# SCH_Driver_RL.net
KiCad netlist of a schematic drawn in Altium Designer
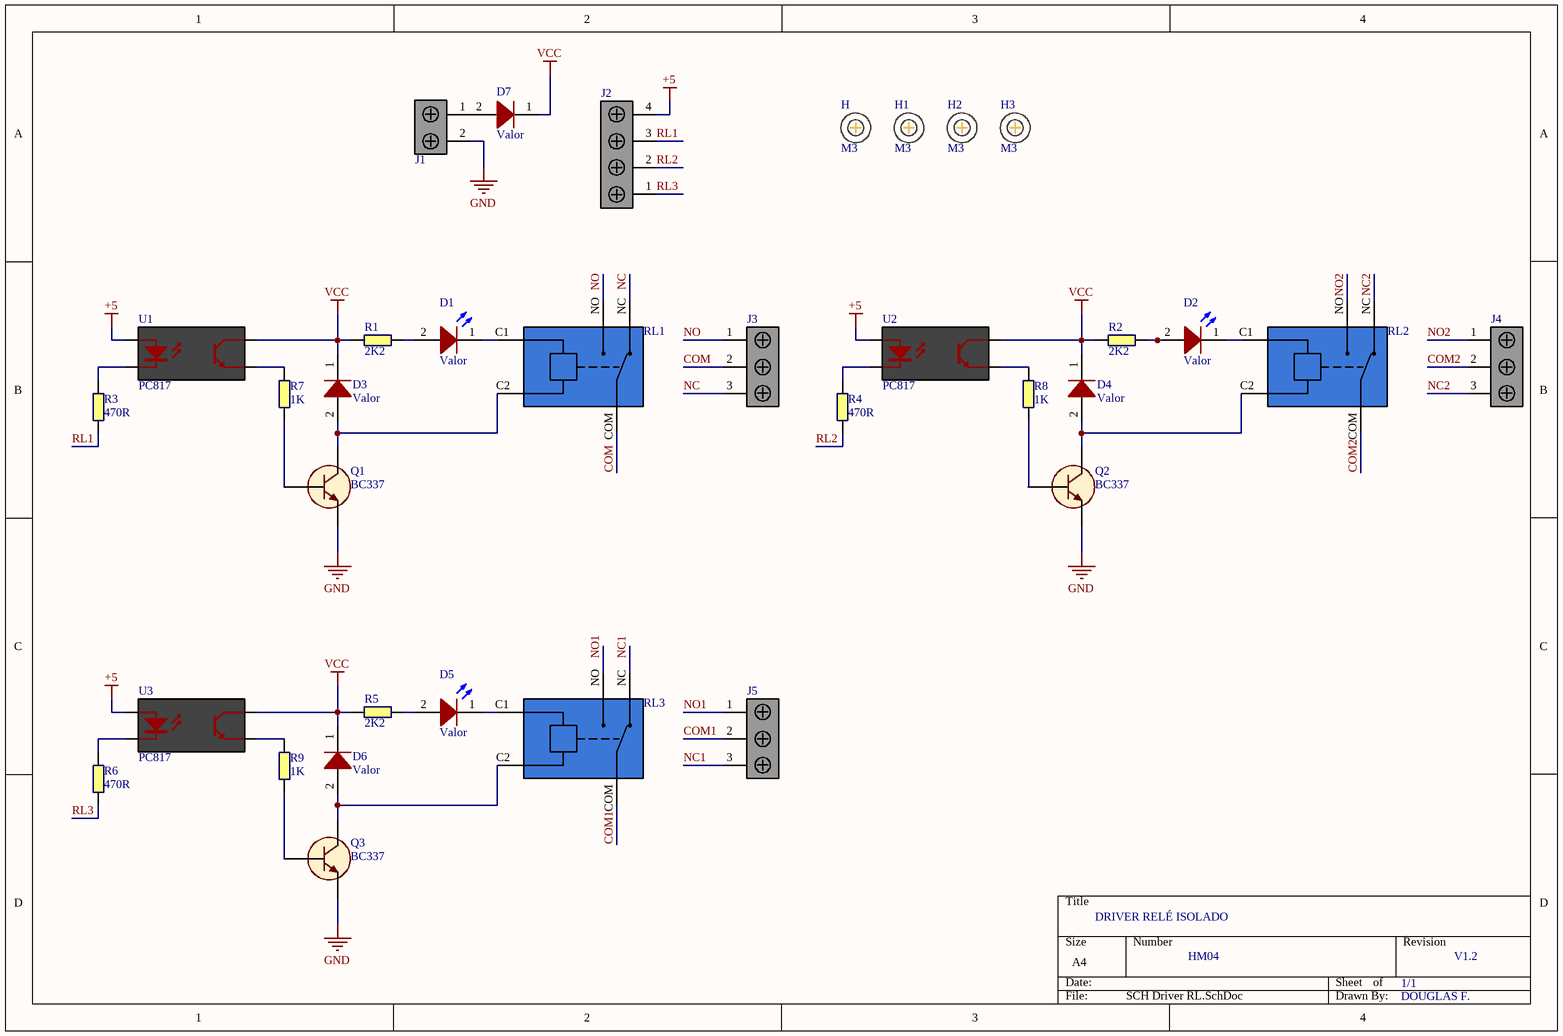
[diagram p0: SCH Driver RL.SchDoc]

(export (version "E")
  (design (tool "Eeschema 10.0.6"))
  (components
    (comp (ref "D1")
      (value "Valor")
      (footprint "LED 3MM")
      (description "Typical RED, GREEN, YELLOW, AMBER GaAs LED")
      (fields (field (name "PUBLISHER") "Altium Limited"))
      (libsource (lib "Driver relé") (part "LED"))
    )
    (comp (ref "D2")
      (value "Valor")
      (footprint "LED 3MM")
      (description "Typical RED, GREEN, YELLOW, AMBER GaAs LED")
      (fields (field (name "PUBLISHER") "Altium Limited"))
      (libsource (lib "Driver relé") (part "LED"))
    )
    (comp (ref "D3")
      (value "Valor")
      (footprint "1N4148 DO-35")
      (description "Diodo rapido")
      (fields (field (name "PUBLISHER") "Altium Limited"))
      (libsource (lib "Driver relé") (part "DIODO 1N4148"))
    )
    (comp (ref "D4")
      (value "Valor")
      (footprint "1N4148 DO-35")
      (description "Diodo rapido")
      (fields (field (name "PUBLISHER") "Altium Limited"))
      (libsource (lib "Driver relé") (part "DIODO 1N4148"))
    )
    (comp (ref "D5")
      (value "Valor")
      (footprint "LED 3MM")
      (description "Typical RED, GREEN, YELLOW, AMBER GaAs LED")
      (fields (field (name "PUBLISHER") "Altium Limited"))
      (libsource (lib "Driver relé") (part "LED"))
    )
    (comp (ref "D6")
      (value "Valor")
      (footprint "1N4148 DO-35")
      (description "Diodo rapido")
      (fields (field (name "PUBLISHER") "Altium Limited"))
      (libsource (lib "Driver relé") (part "DIODO 1N4148"))
    )
    (comp (ref "D7")
      (value "Valor")
      (footprint "1N4007 DO-41")
      (description "Diodo rapido")
      (fields (field (name "PUBLISHER") "Altium Limited"))
      (libsource (lib "Driver relé") (part "DIODO 1N4007"))
    )
    (comp (ref "H") (value "M3") (footprint "Parafuso M3") (libsource (lib "Driver relé") (part "Furo M3")))
    (comp (ref "H1") (value "M3") (footprint "Parafuso M3") (libsource (lib "Driver relé") (part "Furo M3")))
    (comp (ref "H2") (value "M3") (footprint "Parafuso M3") (libsource (lib "Driver relé") (part "Furo M3")))
    (comp (ref "H3") (value "M3") (footprint "Parafuso M3") (libsource (lib "Driver relé") (part "Furo M3")))
    (comp (ref "J1")
      (value "Conector 2v Phoenix")
      (footprint "Terminal block 5mm 2V")
      (description "Block, Terminal; 6 A; 63 V; 5 mm; 26 to 20 AWG; 2; Screw; Soldering; 1.5 kV")
      (fields
        (field (name "MANUFACTURER") "Phoenix Contact")
        (field (name "MANUFACTURER PART NUMBER") "1725656")
      )
      (libsource (lib "Driver relé") (part "TERMINAL BLOCK 2V"))
    )
    (comp (ref "J2")
      (value "TERMINAL BLOCK 4V")
      (footprint "Terminal block 5mm 4V")
      (description "Block, Terminal; 6 A; 63 V; 5 mm; 26 to 20 AWG; 4 Screw; Soldering; 1.5 kV")
      (libsource (lib "Driver relé") (part "TERMINAL BLOCK 4V"))
    )
    (comp (ref "J3")
      (value "Conector 2v Phoenix")
      (footprint "Terminal block 5mm 3V")
      (description "Block, Terminal; 6 A; 63 V; 5 mm; 26 to 20 AWG; 3; Screw; Soldering; 1.5 kV")
      (fields
        (field (name "MANUFACTURER") "Phoenix Contact")
        (field (name "MANUFACTURER PART NUMBER") "1725656")
      )
      (libsource (lib "Driver relé") (part "TERMINAL BLOCK 3V"))
    )
    (comp (ref "J4")
      (value "Conector 2v Phoenix")
      (footprint "Terminal block 5mm 3V")
      (description "Block, Terminal; 6 A; 63 V; 5 mm; 26 to 20 AWG; 3; Screw; Soldering; 1.5 kV")
      (fields
        (field (name "MANUFACTURER") "Phoenix Contact")
        (field (name "MANUFACTURER PART NUMBER") "1725656")
      )
      (libsource (lib "Driver relé") (part "TERMINAL BLOCK 3V"))
    )
    (comp (ref "J5")
      (value "Conector 2v Phoenix")
      (footprint "Terminal block 5mm 3V")
      (description "Block, Terminal; 6 A; 63 V; 5 mm; 26 to 20 AWG; 3; Screw; Soldering; 1.5 kV")
      (fields
        (field (name "MANUFACTURER") "Phoenix Contact")
        (field (name "MANUFACTURER PART NUMBER") "1725656")
      )
      (libsource (lib "Driver relé") (part "TERMINAL BLOCK 3V"))
    )
    (comp (ref "Q1") (value "BC337") (footprint "TO 92") (libsource (lib "Driver relé") (part "BC337")))
    (comp (ref "Q2") (value "BC337") (footprint "TO 92") (libsource (lib "Driver relé") (part "BC337")))
    (comp (ref "Q3") (value "BC337") (footprint "TO 92") (libsource (lib "Driver relé") (part "BC337")))
    (comp (ref "R1")
      (value "2K2")
      (footprint "RES 1/4 PTH")
      (description "Resistor")
      (fields (field (name "PUBLISHER") "Altium Limited"))
      (libsource (lib "") (part "RESISTOR 1/4W_1"))
    )
    (comp (ref "R2")
      (value "2K2")
      (footprint "RES 1/4 PTH")
      (description "Resistor")
      (fields (field (name "PUBLISHER") "Altium Limited"))
      (libsource (lib "") (part "RESISTOR 1/4W_1"))
    )
    (comp (ref "R3")
      (value "470R")
      (footprint "RES 1/4 PTH")
      (description "Resistor")
      (fields (field (name "PUBLISHER") "Altium Limited"))
      (libsource (lib "Driver relé") (part "RESISTOR 1/4W"))
    )
    (comp (ref "R4")
      (value "470R")
      (footprint "RES 1/4 PTH")
      (description "Resistor")
      (fields (field (name "PUBLISHER") "Altium Limited"))
      (libsource (lib "Driver relé") (part "RESISTOR 1/4W"))
    )
    (comp (ref "R5")
      (value "2K2")
      (footprint "RES 1/4 PTH")
      (description "Resistor")
      (fields (field (name "PUBLISHER") "Altium Limited"))
      (libsource (lib "") (part "RESISTOR 1/4W_1"))
    )
    (comp (ref "R6")
      (value "470R")
      (footprint "RES 1/4 PTH")
      (description "Resistor")
      (fields (field (name "PUBLISHER") "Altium Limited"))
      (libsource (lib "Driver relé") (part "RESISTOR 1/4W"))
    )
    (comp (ref "R7")
      (value "1K")
      (footprint "RES 1/4 PTH")
      (description "Resistor")
      (fields (field (name "PUBLISHER") "Altium Limited"))
      (libsource (lib "Driver relé") (part "RESISTOR 1/4W"))
    )
    (comp (ref "R8")
      (value "1K")
      (footprint "RES 1/4 PTH")
      (description "Resistor")
      (fields (field (name "PUBLISHER") "Altium Limited"))
      (libsource (lib "Driver relé") (part "RESISTOR 1/4W"))
    )
    (comp (ref "R9")
      (value "1K")
      (footprint "RES 1/4 PTH")
      (description "Resistor")
      (fields (field (name "PUBLISHER") "Altium Limited"))
      (libsource (lib "Driver relé") (part "RESISTOR 1/4W"))
    )
    (comp (ref "RL1")
      (value "Relé 12v 5p")
      (footprint "RELAY")
      (libsource (lib "Driver relé") (part "Relé 12v 5p"))
    )
    (comp (ref "RL2")
      (value "Relé 12v 5p")
      (footprint "RELAY")
      (libsource (lib "Driver relé") (part "Relé 12v 5p"))
    )
    (comp (ref "RL3")
      (value "Relé 12v 5p")
      (footprint "RELAY")
      (libsource (lib "Driver relé") (part "Relé 12v 5p"))
    )
    (comp (ref "U1") (value "PC817") (footprint "PC817 DIP-4") (libsource (lib "Driver relé") (part "PC817")))
    (comp (ref "U2") (value "PC817") (footprint "PC817 DIP-4") (libsource (lib "Driver relé") (part "PC817")))
    (comp (ref "U3") (value "PC817") (footprint "PC817 DIP-4") (libsource (lib "Driver relé") (part "PC817")))
  )
  (nets
    (net (code "1") (name "+5") (class "Default")
      (node (ref "J2") (pin "4") (pinfunction "4_4") (pintype "passive"))
      (node (ref "U1") (pin "1") (pinfunction "A_1") (pintype "passive"))
      (node (ref "U2") (pin "1") (pinfunction "A_1") (pintype "passive"))
      (node (ref "U3") (pin "1") (pinfunction "A_1") (pintype "passive"))
    )
    (net (code "2") (name "/COM") (class "Default")
      (node (ref "J3") (pin "2") (pinfunction "2_2") (pintype "passive"))
      (node (ref "RL1") (pin "COM") (pinfunction "COM_COM") (pintype "passive"))
    )
    (net (code "3") (name "/COM1") (class "Default")
      (node (ref "J5") (pin "2") (pinfunction "2_2") (pintype "passive"))
      (node (ref "RL3") (pin "COM") (pinfunction "COM_COM") (pintype "passive"))
    )
    (net (code "4") (name "/COM2") (class "Default")
      (node (ref "J4") (pin "2") (pinfunction "2_2") (pintype "passive"))
      (node (ref "RL2") (pin "COM") (pinfunction "COM_COM") (pintype "passive"))
    )
    (net (code "5") (name "/NC") (class "Default")
      (node (ref "J3") (pin "3") (pinfunction "3_3") (pintype "passive"))
      (node (ref "RL1") (pin "NC") (pinfunction "NC_NC") (pintype "passive"))
    )
    (net (code "6") (name "/NC1") (class "Default")
      (node (ref "J5") (pin "3") (pinfunction "3_3") (pintype "passive"))
      (node (ref "RL3") (pin "NC") (pinfunction "NC_NC") (pintype "passive"))
    )
    (net (code "7") (name "/NC2") (class "Default")
      (node (ref "J4") (pin "3") (pinfunction "3_3") (pintype "passive"))
      (node (ref "RL2") (pin "NC") (pinfunction "NC_NC") (pintype "passive"))
    )
    (net (code "8") (name "/NO") (class "Default")
      (node (ref "J3") (pin "1") (pinfunction "1_1") (pintype "passive"))
      (node (ref "RL1") (pin "NO") (pinfunction "NO_NO") (pintype "passive"))
    )
    (net (code "9") (name "/NO1") (class "Default")
      (node (ref "J5") (pin "1") (pinfunction "1_1") (pintype "passive"))
      (node (ref "RL3") (pin "NO") (pinfunction "NO_NO") (pintype "passive"))
    )
    (net (code "10") (name "/NO2") (class "Default")
      (node (ref "J4") (pin "1") (pinfunction "1_1") (pintype "passive"))
      (node (ref "RL2") (pin "NO") (pinfunction "NO_NO") (pintype "passive"))
    )
    (net (code "11") (name "/RL1") (class "Default")
      (node (ref "J2") (pin "3") (pinfunction "3_3") (pintype "passive"))
      (node (ref "R3") (pin "1") (pinfunction "1_1") (pintype "passive"))
    )
    (net (code "12") (name "/RL2") (class "Default")
      (node (ref "J2") (pin "2") (pinfunction "2_2") (pintype "passive"))
      (node (ref "R4") (pin "1") (pinfunction "1_1") (pintype "passive"))
    )
    (net (code "13") (name "/RL3") (class "Default")
      (node (ref "J2") (pin "1") (pinfunction "1_1") (pintype "passive"))
      (node (ref "R6") (pin "1") (pinfunction "1_1") (pintype "passive"))
    )
    (net (code "14") (name "GND") (class "Default")
      (node (ref "J1") (pin "2") (pinfunction "2_2") (pintype "passive"))
      (node (ref "Q1") (pin "3") (pinfunction "E_3") (pintype "passive"))
      (node (ref "Q2") (pin "3") (pinfunction "E_3") (pintype "passive"))
      (node (ref "Q3") (pin "3") (pinfunction "E_3") (pintype "passive"))
    )
    (net (code "15") (name "Net-(D1-1)") (class "Default")
      (node (ref "D1") (pin "2") (pinfunction "1_2") (pintype "passive"))
      (node (ref "R1") (pin "1") (pinfunction "1_1") (pintype "passive"))
    )
    (net (code "16") (name "Net-(D1-2)") (class "Default")
      (node (ref "D1") (pin "1") (pinfunction "2_1") (pintype "passive"))
      (node (ref "RL1") (pin "C1") (pinfunction "COIL_1_C1") (pintype "passive"))
    )
    (net (code "17") (name "Net-(D2-1)") (class "Default")
      (node (ref "D2") (pin "2") (pinfunction "1_2") (pintype "passive"))
      (node (ref "R2") (pin "1") (pinfunction "1_1") (pintype "passive"))
    )
    (net (code "18") (name "Net-(D2-2)") (class "Default")
      (node (ref "D2") (pin "1") (pinfunction "2_1") (pintype "passive"))
      (node (ref "RL2") (pin "C1") (pinfunction "COIL_1_C1") (pintype "passive"))
    )
    (net (code "19") (name "Net-(D5-1)") (class "Default")
      (node (ref "D5") (pin "2") (pinfunction "1_2") (pintype "passive"))
      (node (ref "R5") (pin "1") (pinfunction "1_1") (pintype "passive"))
    )
    (net (code "20") (name "Net-(D5-2)") (class "Default")
      (node (ref "D5") (pin "1") (pinfunction "2_1") (pintype "passive"))
      (node (ref "RL3") (pin "C1") (pinfunction "COIL_1_C1") (pintype "passive"))
    )
    (net (code "21") (name "Net-(D7-Pad2)") (class "Default")
      (node (ref "D7") (pin "2") (pinfunction "2_2") (pintype "passive"))
      (node (ref "J1") (pin "1") (pinfunction "1_1") (pintype "passive"))
    )
    (net (code "22") (name "Net-(Q1-B)") (class "Default")
      (node (ref "Q1") (pin "2") (pinfunction "B_2") (pintype "passive"))
      (node (ref "R7") (pin "1") (pinfunction "1_1") (pintype "passive"))
    )
    (net (code "23") (name "Net-(Q1-C)") (class "Default")
      (node (ref "D3") (pin "2") (pinfunction "2_2") (pintype "passive"))
      (node (ref "Q1") (pin "1") (pinfunction "C_1") (pintype "passive"))
      (node (ref "RL1") (pin "C2") (pinfunction "COIL_2_C2") (pintype "passive"))
    )
    (net (code "24") (name "Net-(Q2-B)") (class "Default")
      (node (ref "Q2") (pin "2") (pinfunction "B_2") (pintype "passive"))
      (node (ref "R8") (pin "1") (pinfunction "1_1") (pintype "passive"))
    )
    (net (code "25") (name "Net-(Q2-C)") (class "Default")
      (node (ref "D4") (pin "2") (pinfunction "2_2") (pintype "passive"))
      (node (ref "Q2") (pin "1") (pinfunction "C_1") (pintype "passive"))
      (node (ref "RL2") (pin "C2") (pinfunction "COIL_2_C2") (pintype "passive"))
    )
    (net (code "26") (name "Net-(Q3-B)") (class "Default")
      (node (ref "Q3") (pin "2") (pinfunction "B_2") (pintype "passive"))
      (node (ref "R9") (pin "1") (pinfunction "1_1") (pintype "passive"))
    )
    (net (code "27") (name "Net-(Q3-C)") (class "Default")
      (node (ref "D6") (pin "2") (pinfunction "2_2") (pintype "passive"))
      (node (ref "Q3") (pin "1") (pinfunction "C_1") (pintype "passive"))
      (node (ref "RL3") (pin "C2") (pinfunction "COIL_2_C2") (pintype "passive"))
    )
    (net (code "28") (name "Net-(U1-E)") (class "Default")
      (node (ref "R7") (pin "2") (pinfunction "2_2") (pintype "passive"))
      (node (ref "U1") (pin "3") (pinfunction "E_3") (pintype "passive"))
    )
    (net (code "29") (name "Net-(U1-K)") (class "Default")
      (node (ref "R3") (pin "2") (pinfunction "2_2") (pintype "passive"))
      (node (ref "U1") (pin "2") (pinfunction "K_2") (pintype "passive"))
    )
    (net (code "30") (name "Net-(U2-E)") (class "Default")
      (node (ref "R8") (pin "2") (pinfunction "2_2") (pintype "passive"))
      (node (ref "U2") (pin "3") (pinfunction "E_3") (pintype "passive"))
    )
    (net (code "31") (name "Net-(U2-K)") (class "Default")
      (node (ref "R4") (pin "2") (pinfunction "2_2") (pintype "passive"))
      (node (ref "U2") (pin "2") (pinfunction "K_2") (pintype "passive"))
    )
    (net (code "32") (name "Net-(U3-E)") (class "Default")
      (node (ref "R9") (pin "2") (pinfunction "2_2") (pintype "passive"))
      (node (ref "U3") (pin "3") (pinfunction "E_3") (pintype "passive"))
    )
    (net (code "33") (name "Net-(U3-K)") (class "Default")
      (node (ref "R6") (pin "2") (pinfunction "2_2") (pintype "passive"))
      (node (ref "U3") (pin "2") (pinfunction "K_2") (pintype "passive"))
    )
    (net (code "34") (name "VCC") (class "Default")
      (node (ref "D3") (pin "1") (pinfunction "1_1") (pintype "passive"))
      (node (ref "D4") (pin "1") (pinfunction "1_1") (pintype "passive"))
      (node (ref "D6") (pin "1") (pinfunction "1_1") (pintype "passive"))
      (node (ref "D7") (pin "1") (pinfunction "1_1") (pintype "passive"))
      (node (ref "R1") (pin "2") (pinfunction "2_2") (pintype "passive"))
      (node (ref "R2") (pin "2") (pinfunction "2_2") (pintype "passive"))
      (node (ref "R5") (pin "2") (pinfunction "2_2") (pintype "passive"))
      (node (ref "U1") (pin "4") (pinfunction "C_4") (pintype "passive"))
      (node (ref "U2") (pin "4") (pinfunction "C_4") (pintype "passive"))
      (node (ref "U3") (pin "4") (pinfunction "C_4") (pintype "passive"))
    )
  )
)
